# JW24A10L_revA.net
KiCad netlist of a schematic drawn in EAGLE
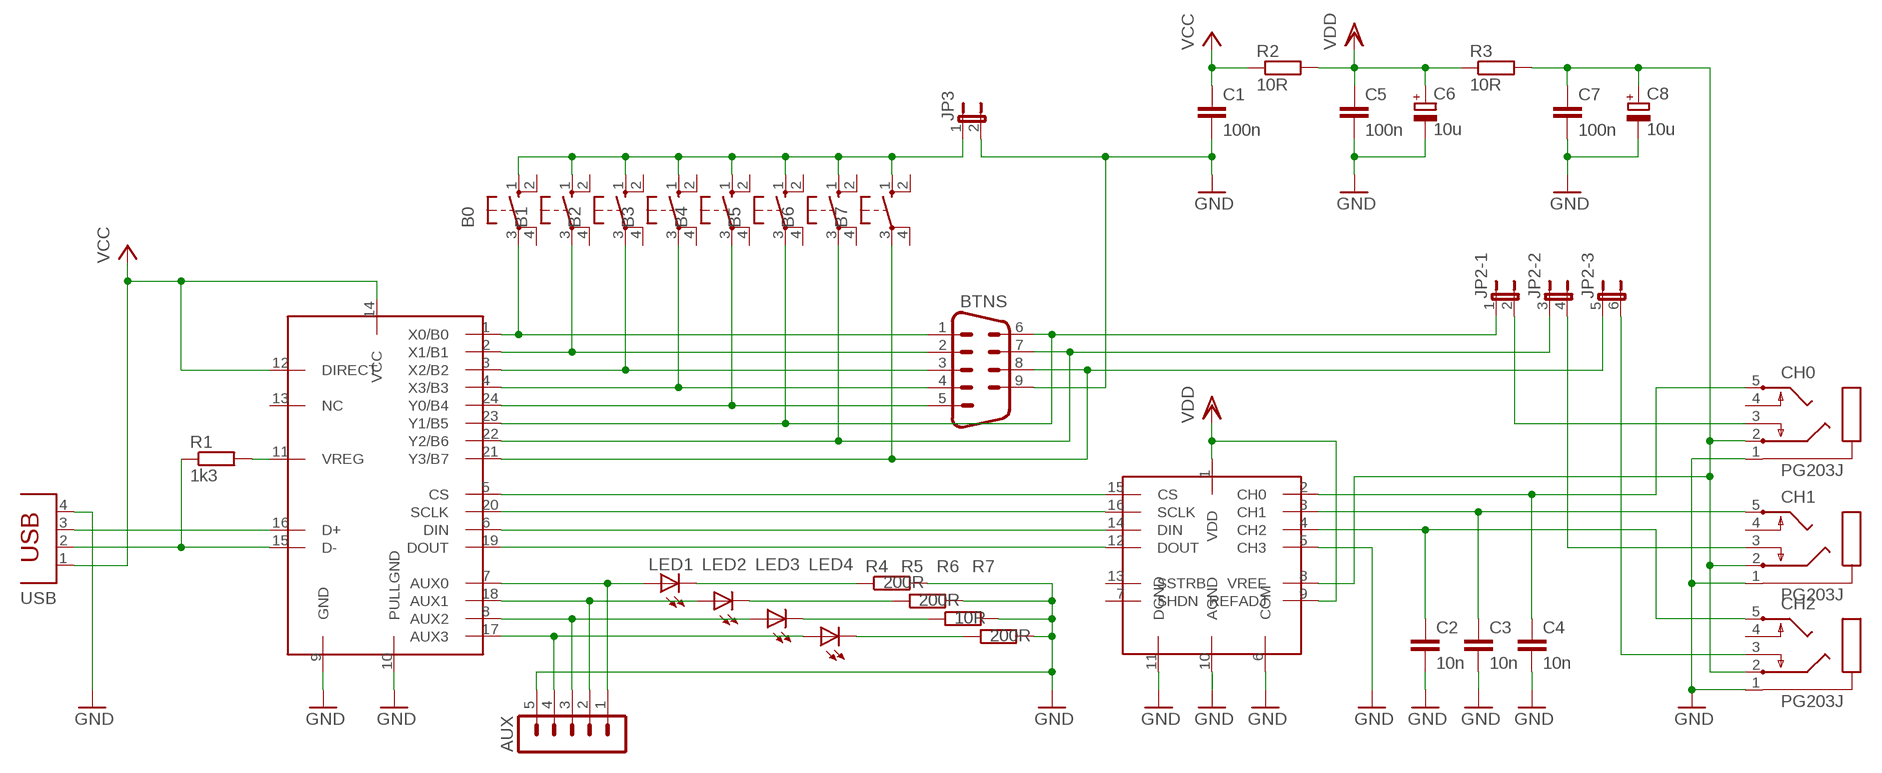
[diagram p0: schematic, sheet 1]

(export (version "E")
  (design (tool "Eeschema 10.0.6"))
  (components
    (comp (ref "AUX")
      (value "MA05-1")
      (footprint "eagle-import:MA05-1")
      (libsource (lib "eagle-import") (part "MA05-1"))
    )
    (comp (ref "B0")
      (value "10-XX")
      (footprint "eagle-import:B3F-10XX")
      (fields (field (name "MPN") "B3F-1000"))
      (libsource (lib "eagle-import") (part "10-XX"))
    )
    (comp (ref "B1")
      (value "10-XX")
      (footprint "eagle-import:B3F-10XX")
      (fields (field (name "MPN") "B3F-1000"))
      (libsource (lib "eagle-import") (part "10-XX"))
    )
    (comp (ref "B2")
      (value "10-XX")
      (footprint "eagle-import:B3F-10XX")
      (fields
        (field (name "MPN") "B3F-1000")
        (field (name "MPN_1") "B3F-1000")
        (field (name "OC_FARNELL") "176432")
        (field (name "OC_NEWARK") "36M3542")
      )
      (libsource (lib "eagle-import") (part "10-XX"))
    )
    (comp (ref "B3")
      (value "10-XX")
      (footprint "eagle-import:B3F-10XX")
      (fields
        (field (name "MPN") "B3F-1000")
        (field (name "MPN_1") "B3F-1000")
        (field (name "OC_FARNELL") "176432")
        (field (name "OC_NEWARK") "36M3542")
      )
      (libsource (lib "eagle-import") (part "10-XX"))
    )
    (comp (ref "B4")
      (value "10-XX")
      (footprint "eagle-import:B3F-10XX")
      (fields
        (field (name "MPN") "B3F-1000")
        (field (name "MPN_1") "B3F-1000")
        (field (name "OC_FARNELL") "176432")
        (field (name "OC_NEWARK") "36M3542")
      )
      (libsource (lib "eagle-import") (part "10-XX"))
    )
    (comp (ref "B5")
      (value "10-XX")
      (footprint "eagle-import:B3F-10XX")
      (fields
        (field (name "MPN") "B3F-1000")
        (field (name "MPN_1") "B3F-1000")
        (field (name "OC_FARNELL") "176432")
        (field (name "OC_NEWARK") "36M3542")
      )
      (libsource (lib "eagle-import") (part "10-XX"))
    )
    (comp (ref "B6")
      (value "10-XX")
      (footprint "eagle-import:B3F-10XX")
      (fields
        (field (name "MPN") "B3F-1000")
        (field (name "MPN_1") "B3F-1000")
        (field (name "OC_FARNELL") "176432")
        (field (name "OC_NEWARK") "36M3542")
      )
      (libsource (lib "eagle-import") (part "10-XX"))
    )
    (comp (ref "B7")
      (value "10-XX")
      (footprint "eagle-import:B3F-10XX")
      (fields
        (field (name "MPN") "B3F-1000")
        (field (name "MPN_1") "B3F-1000")
        (field (name "OC_FARNELL") "176432")
        (field (name "OC_NEWARK") "36M3542")
      )
      (libsource (lib "eagle-import") (part "10-XX"))
    )
    (comp (ref "BTNS")
      (value "M09HP")
      (footprint "eagle-import:M09HP")
      (libsource (lib "eagle-import") (part "M09HP"))
    )
    (comp (ref "C1")
      (value "100n")
      (footprint "eagle-import:C025-025X050")
      (libsource (lib "eagle-import") (part "C-EU025-025X050"))
    )
    (comp (ref "C2")
      (value "10n")
      (footprint "eagle-import:C025-025X050")
      (libsource (lib "eagle-import") (part "C-EU025-025X050"))
    )
    (comp (ref "C3")
      (value "10n")
      (footprint "eagle-import:C025-025X050")
      (libsource (lib "eagle-import") (part "C-EU025-025X050"))
    )
    (comp (ref "C4")
      (value "10n")
      (footprint "eagle-import:C025-025X050")
      (libsource (lib "eagle-import") (part "C-EU025-025X050"))
    )
    (comp (ref "C5")
      (value "100n")
      (footprint "eagle-import:C025-025X050")
      (libsource (lib "eagle-import") (part "C-EU025-025X050"))
    )
    (comp (ref "C6")
      (value "10u")
      (footprint "eagle-import:E2-5")
      (libsource (lib "eagle-import") (part "CPOL-EUE2-5"))
    )
    (comp (ref "C7")
      (value "100n")
      (footprint "eagle-import:C025-025X050")
      (libsource (lib "eagle-import") (part "C-EU025-025X050"))
    )
    (comp (ref "C8")
      (value "10u")
      (footprint "eagle-import:E2-5")
      (libsource (lib "eagle-import") (part "CPOL-EUE2-5"))
    )
    (comp (ref "CH0")
      (value "PG203J")
      (footprint "eagle-import:PG203J")
      (libsource (lib "eagle-import") (part "PG203J"))
    )
    (comp (ref "CH1")
      (value "PG203J")
      (footprint "eagle-import:PG203J")
      (libsource (lib "eagle-import") (part "PG203J"))
    )
    (comp (ref "CH2")
      (value "PG203J")
      (footprint "eagle-import:PG203J")
      (libsource (lib "eagle-import") (part "PG203J"))
    )
    (comp (ref "JP2")
      (value "JP3QE")
      (footprint "eagle-import:JP3Q")
      (libsource (lib "eagle-import") (part "JP3QE"))
    )
    (comp (ref "JP3")
      (value "JP1E")
      (footprint "eagle-import:JP1")
      (libsource (lib "eagle-import") (part "JP1E"))
    )
    (comp (ref "LED1")
      (value "LED3MM")
      (footprint "eagle-import:LED3MM")
      (libsource (lib "eagle-import") (part "LED3MM"))
    )
    (comp (ref "LED2")
      (value "LED3MM")
      (footprint "eagle-import:LED3MM")
      (libsource (lib "eagle-import") (part "LED3MM"))
    )
    (comp (ref "LED3")
      (value "LED3MM")
      (footprint "eagle-import:LED3MM")
      (libsource (lib "eagle-import") (part "LED3MM"))
    )
    (comp (ref "LED4")
      (value "LED3MM")
      (footprint "eagle-import:LED3MM")
      (libsource (lib "eagle-import") (part "LED3MM"))
    )
    (comp (ref "R1")
      (value "1k3")
      (footprint "eagle-import:0204_7")
      (libsource (lib "eagle-import") (part "R-EU_0204/7"))
    )
    (comp (ref "R2")
      (value "10R")
      (footprint "eagle-import:0204_7")
      (libsource (lib "eagle-import") (part "R-EU_0204/7"))
    )
    (comp (ref "R3")
      (value "10R")
      (footprint "eagle-import:0204_7")
      (libsource (lib "eagle-import") (part "R-EU_0204/7"))
    )
    (comp (ref "R4")
      (value "200R")
      (footprint "eagle-import:0204_7")
      (libsource (lib "eagle-import") (part "R-EU_0204/7"))
    )
    (comp (ref "R5")
      (value "200R")
      (footprint "eagle-import:0204_7")
      (libsource (lib "eagle-import") (part "R-EU_0204/7"))
    )
    (comp (ref "R6")
      (value "10R")
      (footprint "eagle-import:0204_7")
      (libsource (lib "eagle-import") (part "R-EU_0204/7"))
    )
    (comp (ref "R7")
      (value "200R")
      (footprint "eagle-import:0204_7")
      (libsource (lib "eagle-import") (part "R-EU_0204/7"))
    )
    (comp (ref "U$1")
      (value "MAX1249")
      (footprint "eagle-import:DIL16")
      (libsource (lib "eagle-import") (part "MAX1249"))
    )
    (comp (ref "U$2")
      (value "JW24A10L")
      (footprint "eagle-import:DIL24-3")
      (libsource (lib "eagle-import") (part "JW24A10L"))
    )
    (comp (ref "USB")
      (value "PN61729")
      (footprint "eagle-import:PN61729")
      (libsource (lib "eagle-import") (part "PN61729"))
    )
  )
  (nets
    (net (code "1") (name "GND") (class "Default")
      (node (ref "AUX") (pin "5") (pinfunction "5_5") (pintype "passive"))
      (node (ref "BTNS") (pin "9") (pinfunction "9_9") (pintype "passive"))
      (node (ref "C1") (pin "2") (pinfunction "2_2") (pintype "passive"))
      (node (ref "C2") (pin "2") (pinfunction "2_2") (pintype "passive"))
      (node (ref "C3") (pin "2") (pinfunction "2_2") (pintype "passive"))
      (node (ref "C4") (pin "2") (pinfunction "2_2") (pintype "passive"))
      (node (ref "C5") (pin "2") (pinfunction "2_2") (pintype "passive"))
      (node (ref "C6") (pin "-") (pinfunction "-_-") (pintype "passive"))
      (node (ref "C7") (pin "2") (pinfunction "2_2") (pintype "passive"))
      (node (ref "C8") (pin "-") (pinfunction "-_-") (pintype "passive"))
      (node (ref "CH0") (pin "1") (pinfunction "1_1") (pintype "passive"))
      (node (ref "CH1") (pin "1") (pinfunction "1_1") (pintype "passive"))
      (node (ref "CH2") (pin "1") (pinfunction "1_1") (pintype "passive"))
      (node (ref "JP3") (pin "2") (pinfunction "2_2") (pintype "passive"))
      (node (ref "R4") (pin "2") (pinfunction "2_2") (pintype "passive"))
      (node (ref "R5") (pin "2") (pinfunction "2_2") (pintype "passive"))
      (node (ref "R6") (pin "2") (pinfunction "2_2") (pintype "passive"))
      (node (ref "R7") (pin "2") (pinfunction "2_2") (pintype "passive"))
      (node (ref "U$1") (pin "10") (pinfunction "AGND_10") (pintype "power_in"))
      (node (ref "U$1") (pin "11") (pinfunction "DGND_11") (pintype "power_in"))
      (node (ref "U$1") (pin "5") (pinfunction "CH3_5") (pintype "input"))
      (node (ref "U$1") (pin "6") (pinfunction "COM_6") (pintype "bidirectional"))
      (node (ref "U$2") (pin "10") (pinfunction "PULLGND_10") (pintype "power_in"))
      (node (ref "U$2") (pin "9") (pinfunction "GND_9") (pintype "power_in"))
      (node (ref "USB") (pin "4") (pinfunction "4_4") (pintype "passive"))
    )
    (net (code "2") (name "Net-(B0-P)") (class "Default")
      (node (ref "B0") (pin "3") (pinfunction "P_3") (pintype "passive"))
      (node (ref "BTNS") (pin "1") (pinfunction "1_1") (pintype "passive"))
      (node (ref "U$2") (pin "1") (pinfunction "X0/B0_1") (pintype "bidirectional"))
    )
    (net (code "3") (name "Net-(B0-S)") (class "Default")
      (node (ref "B0") (pin "1") (pinfunction "S_1") (pintype "passive"))
      (node (ref "B1") (pin "1") (pinfunction "S_1") (pintype "passive"))
      (node (ref "B2") (pin "1") (pinfunction "S_1") (pintype "passive"))
      (node (ref "B3") (pin "1") (pinfunction "S_1") (pintype "passive"))
      (node (ref "B4") (pin "1") (pinfunction "S_1") (pintype "passive"))
      (node (ref "B5") (pin "1") (pinfunction "S_1") (pintype "passive"))
      (node (ref "B6") (pin "1") (pinfunction "S_1") (pintype "passive"))
      (node (ref "B7") (pin "1") (pinfunction "S_1") (pintype "passive"))
      (node (ref "JP3") (pin "1") (pinfunction "1_1") (pintype "passive"))
    )
    (net (code "4") (name "Net-(B1-P)") (class "Default")
      (node (ref "B1") (pin "3") (pinfunction "P_3") (pintype "passive"))
      (node (ref "BTNS") (pin "2") (pinfunction "2_2") (pintype "passive"))
      (node (ref "U$2") (pin "2") (pinfunction "X1/B1_2") (pintype "bidirectional"))
    )
    (net (code "5") (name "Net-(B2-P)") (class "Default")
      (node (ref "B2") (pin "3") (pinfunction "P_3") (pintype "passive"))
      (node (ref "BTNS") (pin "3") (pinfunction "3_3") (pintype "passive"))
      (node (ref "U$2") (pin "3") (pinfunction "X2/B2_3") (pintype "bidirectional"))
    )
    (net (code "6") (name "Net-(B3-P)") (class "Default")
      (node (ref "B3") (pin "3") (pinfunction "P_3") (pintype "passive"))
      (node (ref "BTNS") (pin "4") (pinfunction "4_4") (pintype "passive"))
      (node (ref "U$2") (pin "4") (pinfunction "X3/B3_4") (pintype "bidirectional"))
    )
    (net (code "7") (name "Net-(B4-P)") (class "Default")
      (node (ref "B4") (pin "3") (pinfunction "P_3") (pintype "passive"))
      (node (ref "BTNS") (pin "5") (pinfunction "5_5") (pintype "passive"))
      (node (ref "U$2") (pin "24") (pinfunction "Y0/B4_24") (pintype "bidirectional"))
    )
    (net (code "8") (name "Net-(B5-P)") (class "Default")
      (node (ref "B5") (pin "3") (pinfunction "P_3") (pintype "passive"))
      (node (ref "BTNS") (pin "6") (pinfunction "6_6") (pintype "passive"))
      (node (ref "JP2") (pin "1") (pinfunction "1_1") (pintype "passive"))
      (node (ref "U$2") (pin "23") (pinfunction "Y1/B5_23") (pintype "bidirectional"))
    )
    (net (code "9") (name "Net-(B6-P)") (class "Default")
      (node (ref "B6") (pin "3") (pinfunction "P_3") (pintype "passive"))
      (node (ref "BTNS") (pin "7") (pinfunction "7_7") (pintype "passive"))
      (node (ref "JP2") (pin "3") (pinfunction "1_3") (pintype "passive"))
      (node (ref "U$2") (pin "22") (pinfunction "Y2/B6_22") (pintype "bidirectional"))
    )
    (net (code "10") (name "Net-(B7-P)") (class "Default")
      (node (ref "B7") (pin "3") (pinfunction "P_3") (pintype "passive"))
      (node (ref "BTNS") (pin "8") (pinfunction "8_8") (pintype "passive"))
      (node (ref "JP2") (pin "5") (pinfunction "1_5") (pintype "passive"))
      (node (ref "U$2") (pin "21") (pinfunction "Y3/B7_21") (pintype "bidirectional"))
    )
    (net (code "11") (name "Net-(CH0-Pad3)") (class "Default")
      (node (ref "CH0") (pin "3") (pinfunction "3_3") (pintype "passive"))
      (node (ref "JP2") (pin "2") (pinfunction "2_2") (pintype "passive"))
    )
    (net (code "12") (name "Net-(JP2B-2)") (class "Default")
      (node (ref "CH1") (pin "3") (pinfunction "3_3") (pintype "passive"))
      (node (ref "JP2") (pin "4") (pinfunction "2_4") (pintype "passive"))
    )
    (net (code "13") (name "Net-(JP2C-2)") (class "Default")
      (node (ref "CH2") (pin "3") (pinfunction "3_3") (pintype "passive"))
      (node (ref "JP2") (pin "6") (pinfunction "2_6") (pintype "passive"))
    )
    (net (code "14") (name "Net-(LED1-C)") (class "Default")
      (node (ref "LED1") (pin "K") (pinfunction "C_K") (pintype "passive"))
      (node (ref "R4") (pin "1") (pinfunction "1_1") (pintype "passive"))
    )
    (net (code "15") (name "Net-(LED2-C)") (class "Default")
      (node (ref "LED2") (pin "K") (pinfunction "C_K") (pintype "passive"))
      (node (ref "R5") (pin "1") (pinfunction "1_1") (pintype "passive"))
    )
    (net (code "16") (name "Net-(LED3-C)") (class "Default")
      (node (ref "LED3") (pin "K") (pinfunction "C_K") (pintype "passive"))
      (node (ref "R6") (pin "1") (pinfunction "1_1") (pintype "passive"))
    )
    (net (code "17") (name "Net-(LED4-C)") (class "Default")
      (node (ref "LED4") (pin "K") (pinfunction "C_K") (pintype "passive"))
      (node (ref "R7") (pin "1") (pinfunction "1_1") (pintype "passive"))
    )
    (net (code "18") (name "Net-(U$1-CH0)") (class "Default")
      (node (ref "C4") (pin "1") (pinfunction "1_1") (pintype "passive"))
      (node (ref "CH0") (pin "5") (pinfunction "5_5") (pintype "passive"))
      (node (ref "U$1") (pin "2") (pinfunction "CH0_2") (pintype "input"))
    )
    (net (code "19") (name "Net-(U$1-CH1)") (class "Default")
      (node (ref "C3") (pin "1") (pinfunction "1_1") (pintype "passive"))
      (node (ref "CH1") (pin "5") (pinfunction "5_5") (pintype "passive"))
      (node (ref "U$1") (pin "3") (pinfunction "CH1_3") (pintype "input"))
    )
    (net (code "20") (name "Net-(U$1-CH2)") (class "Default")
      (node (ref "C2") (pin "1") (pinfunction "1_1") (pintype "passive"))
      (node (ref "CH2") (pin "5") (pinfunction "5_5") (pintype "passive"))
      (node (ref "U$1") (pin "4") (pinfunction "CH2_4") (pintype "input"))
    )
    (net (code "21") (name "Net-(U$1-CS)") (class "Default")
      (node (ref "U$1") (pin "15") (pinfunction "CS_15") (pintype "bidirectional"))
      (node (ref "U$2") (pin "5") (pinfunction "CS_5") (pintype "bidirectional"))
    )
    (net (code "22") (name "Net-(U$1-DIN)") (class "Default")
      (node (ref "U$1") (pin "14") (pinfunction "DIN_14") (pintype "bidirectional"))
      (node (ref "U$2") (pin "6") (pinfunction "DIN_6") (pintype "bidirectional"))
    )
    (net (code "23") (name "Net-(U$1-DOUT)") (class "Default")
      (node (ref "U$1") (pin "12") (pinfunction "DOUT_12") (pintype "bidirectional"))
      (node (ref "U$2") (pin "19") (pinfunction "DOUT_19") (pintype "bidirectional"))
    )
    (net (code "24") (name "Net-(U$1-SCLK)") (class "Default")
      (node (ref "U$1") (pin "16") (pinfunction "SCLK_16") (pintype "bidirectional"))
      (node (ref "U$2") (pin "20") (pinfunction "SCLK_20") (pintype "bidirectional"))
    )
    (net (code "25") (name "Net-(U$1-VREF)") (class "Default")
      (node (ref "C7") (pin "1") (pinfunction "1_1") (pintype "passive"))
      (node (ref "C8") (pin "+") (pinfunction "+_+") (pintype "passive"))
      (node (ref "CH0") (pin "2") (pinfunction "2_2") (pintype "passive"))
      (node (ref "CH1") (pin "2") (pinfunction "2_2") (pintype "passive"))
      (node (ref "CH2") (pin "2") (pinfunction "2_2") (pintype "passive"))
      (node (ref "R3") (pin "2") (pinfunction "2_2") (pintype "passive"))
      (node (ref "U$1") (pin "8") (pinfunction "VREF_8") (pintype "bidirectional"))
    )
    (net (code "26") (name "Net-(U$2-AUX0)") (class "Default")
      (node (ref "AUX") (pin "1") (pinfunction "1_1") (pintype "passive"))
      (node (ref "LED1") (pin "A") (pinfunction "A_A") (pintype "passive"))
      (node (ref "U$2") (pin "7") (pinfunction "AUX0_7") (pintype "power_in"))
    )
    (net (code "27") (name "Net-(U$2-AUX1)") (class "Default")
      (node (ref "AUX") (pin "2") (pinfunction "2_2") (pintype "passive"))
      (node (ref "LED2") (pin "A") (pinfunction "A_A") (pintype "passive"))
      (node (ref "U$2") (pin "18") (pinfunction "AUX1_18") (pintype "power_in"))
    )
    (net (code "28") (name "Net-(U$2-AUX2)") (class "Default")
      (node (ref "AUX") (pin "3") (pinfunction "3_3") (pintype "passive"))
      (node (ref "LED3") (pin "A") (pinfunction "A_A") (pintype "passive"))
      (node (ref "U$2") (pin "8") (pinfunction "AUX2_8") (pintype "power_in"))
    )
    (net (code "29") (name "Net-(U$2-AUX3)") (class "Default")
      (node (ref "AUX") (pin "4") (pinfunction "4_4") (pintype "passive"))
      (node (ref "LED4") (pin "A") (pinfunction "A_A") (pintype "passive"))
      (node (ref "U$2") (pin "17") (pinfunction "AUX3_17") (pintype "power_in"))
    )
    (net (code "30") (name "Net-(U$2-D+)") (class "Default")
      (node (ref "U$2") (pin "16") (pinfunction "D+_16") (pintype "bidirectional"))
      (node (ref "USB") (pin "3") (pinfunction "3_3") (pintype "passive"))
    )
    (net (code "31") (name "Net-(U$2-D-)") (class "Default")
      (node (ref "R1") (pin "1") (pinfunction "1_1") (pintype "passive"))
      (node (ref "U$2") (pin "15") (pinfunction "D-_15") (pintype "bidirectional"))
      (node (ref "USB") (pin "2") (pinfunction "2_2") (pintype "passive"))
    )
    (net (code "32") (name "Net-(U$2-VREG)") (class "Default")
      (node (ref "R1") (pin "2") (pinfunction "2_2") (pintype "passive"))
      (node (ref "U$2") (pin "11") (pinfunction "VREG_11") (pintype "bidirectional"))
    )
    (net (code "33") (name "VCC") (class "Default")
      (node (ref "C1") (pin "1") (pinfunction "1_1") (pintype "passive"))
      (node (ref "R2") (pin "1") (pinfunction "1_1") (pintype "passive"))
      (node (ref "U$2") (pin "12") (pinfunction "DIRECT_12") (pintype "bidirectional"))
      (node (ref "U$2") (pin "14") (pinfunction "VCC_14") (pintype "power_in"))
      (node (ref "USB") (pin "1") (pinfunction "1_1") (pintype "passive"))
    )
    (net (code "34") (name "VDD") (class "Default")
      (node (ref "C5") (pin "1") (pinfunction "1_1") (pintype "passive"))
      (node (ref "C6") (pin "+") (pinfunction "+_+") (pintype "passive"))
      (node (ref "R2") (pin "2") (pinfunction "2_2") (pintype "passive"))
      (node (ref "R3") (pin "1") (pinfunction "1_1") (pintype "passive"))
      (node (ref "U$1") (pin "1") (pinfunction "VDD_1") (pintype "power_in"))
      (node (ref "U$1") (pin "9") (pinfunction "REFADJ_9") (pintype "bidirectional"))
    )
    (net (code "35") (name "unconnected-(B0-P1-Pad4)") (class "Default")
      (node (ref "B0") (pin "4") (pinfunction "P1_4") (pintype "passive"))
    )
    (net (code "36") (name "unconnected-(B0-S1-Pad2)") (class "Default")
      (node (ref "B0") (pin "2") (pinfunction "S1_2") (pintype "passive"))
    )
    (net (code "37") (name "unconnected-(B1-P1-Pad4)") (class "Default")
      (node (ref "B1") (pin "4") (pinfunction "P1_4") (pintype "passive"))
    )
    (net (code "38") (name "unconnected-(B1-S1-Pad2)") (class "Default")
      (node (ref "B1") (pin "2") (pinfunction "S1_2") (pintype "passive"))
    )
    (net (code "39") (name "unconnected-(B2-P1-Pad4)") (class "Default")
      (node (ref "B2") (pin "4") (pinfunction "P1_4") (pintype "passive"))
    )
    (net (code "40") (name "unconnected-(B2-S1-Pad2)") (class "Default")
      (node (ref "B2") (pin "2") (pinfunction "S1_2") (pintype "passive"))
    )
    (net (code "41") (name "unconnected-(B3-P1-Pad4)") (class "Default")
      (node (ref "B3") (pin "4") (pinfunction "P1_4") (pintype "passive"))
    )
    (net (code "42") (name "unconnected-(B3-S1-Pad2)") (class "Default")
      (node (ref "B3") (pin "2") (pinfunction "S1_2") (pintype "passive"))
    )
    (net (code "43") (name "unconnected-(B4-P1-Pad4)") (class "Default")
      (node (ref "B4") (pin "4") (pinfunction "P1_4") (pintype "passive"))
    )
    (net (code "44") (name "unconnected-(B4-S1-Pad2)") (class "Default")
      (node (ref "B4") (pin "2") (pinfunction "S1_2") (pintype "passive"))
    )
    (net (code "45") (name "unconnected-(B5-P1-Pad4)") (class "Default")
      (node (ref "B5") (pin "4") (pinfunction "P1_4") (pintype "passive"))
    )
    (net (code "46") (name "unconnected-(B5-S1-Pad2)") (class "Default")
      (node (ref "B5") (pin "2") (pinfunction "S1_2") (pintype "passive"))
    )
    (net (code "47") (name "unconnected-(B6-P1-Pad4)") (class "Default")
      (node (ref "B6") (pin "4") (pinfunction "P1_4") (pintype "passive"))
    )
    (net (code "48") (name "unconnected-(B6-S1-Pad2)") (class "Default")
      (node (ref "B6") (pin "2") (pinfunction "S1_2") (pintype "passive"))
    )
    (net (code "49") (name "unconnected-(B7-P1-Pad4)") (class "Default")
      (node (ref "B7") (pin "4") (pinfunction "P1_4") (pintype "passive"))
    )
    (net (code "50") (name "unconnected-(B7-S1-Pad2)") (class "Default")
      (node (ref "B7") (pin "2") (pinfunction "S1_2") (pintype "passive"))
    )
    (net (code "51") (name "unconnected-(CH0-Pad4)") (class "Default")
      (node (ref "CH0") (pin "4") (pinfunction "4_4") (pintype "passive"))
    )
    (net (code "52") (name "unconnected-(CH1-Pad4)") (class "Default")
      (node (ref "CH1") (pin "4") (pinfunction "4_4") (pintype "passive"))
    )
    (net (code "53") (name "unconnected-(CH2-Pad4)") (class "Default")
      (node (ref "CH2") (pin "4") (pinfunction "4_4") (pintype "passive"))
    )
    (net (code "54") (name "unconnected-(U$1-SHDN-Pad7)") (class "Default")
      (node (ref "U$1") (pin "7") (pinfunction "SHDN_7") (pintype "bidirectional"))
    )
    (net (code "55") (name "unconnected-(U$1-SSTRB-Pad13)") (class "Default")
      (node (ref "U$1") (pin "13") (pinfunction "SSTRB_13") (pintype "bidirectional"))
    )
    (net (code "56") (name "unconnected-(U$2-NC-Pad13)") (class "Default")
      (node (ref "U$2") (pin "13") (pinfunction "NC_13") (pintype "bidirectional"))
    )
  )
)
